# Project-PowerSwitch-005.net
KiCad netlist of a schematic drawn in EAGLE
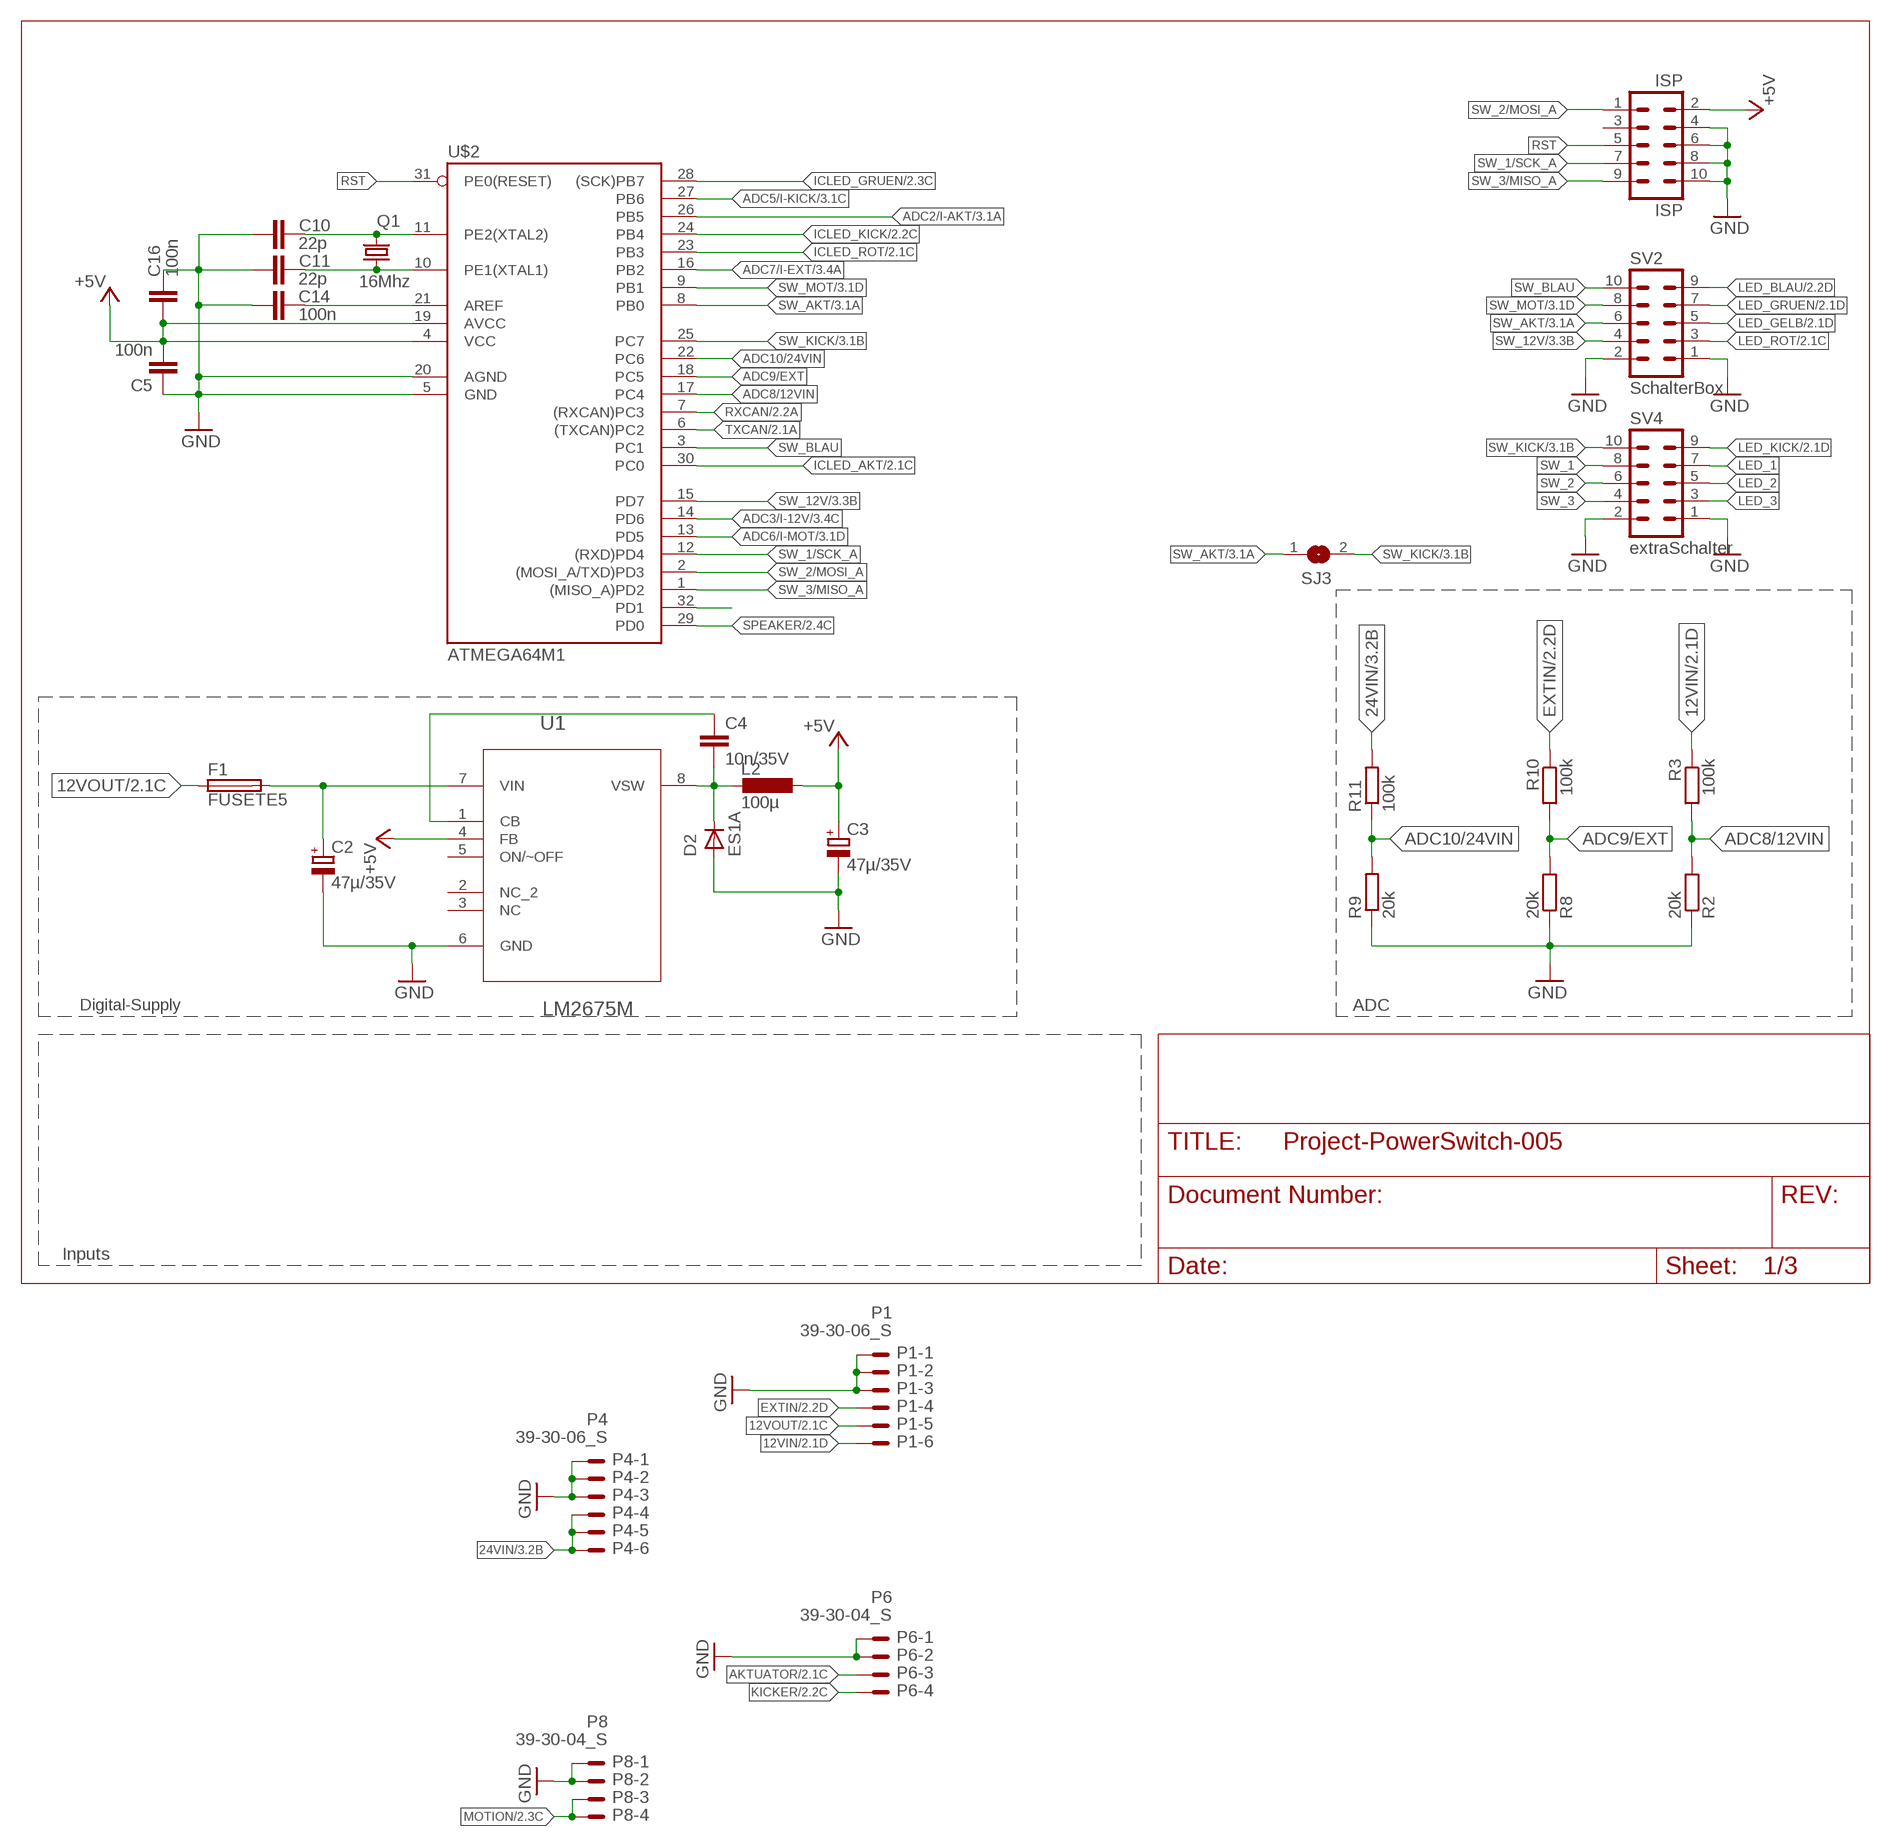
[diagram p0: schematic, sheet 1]
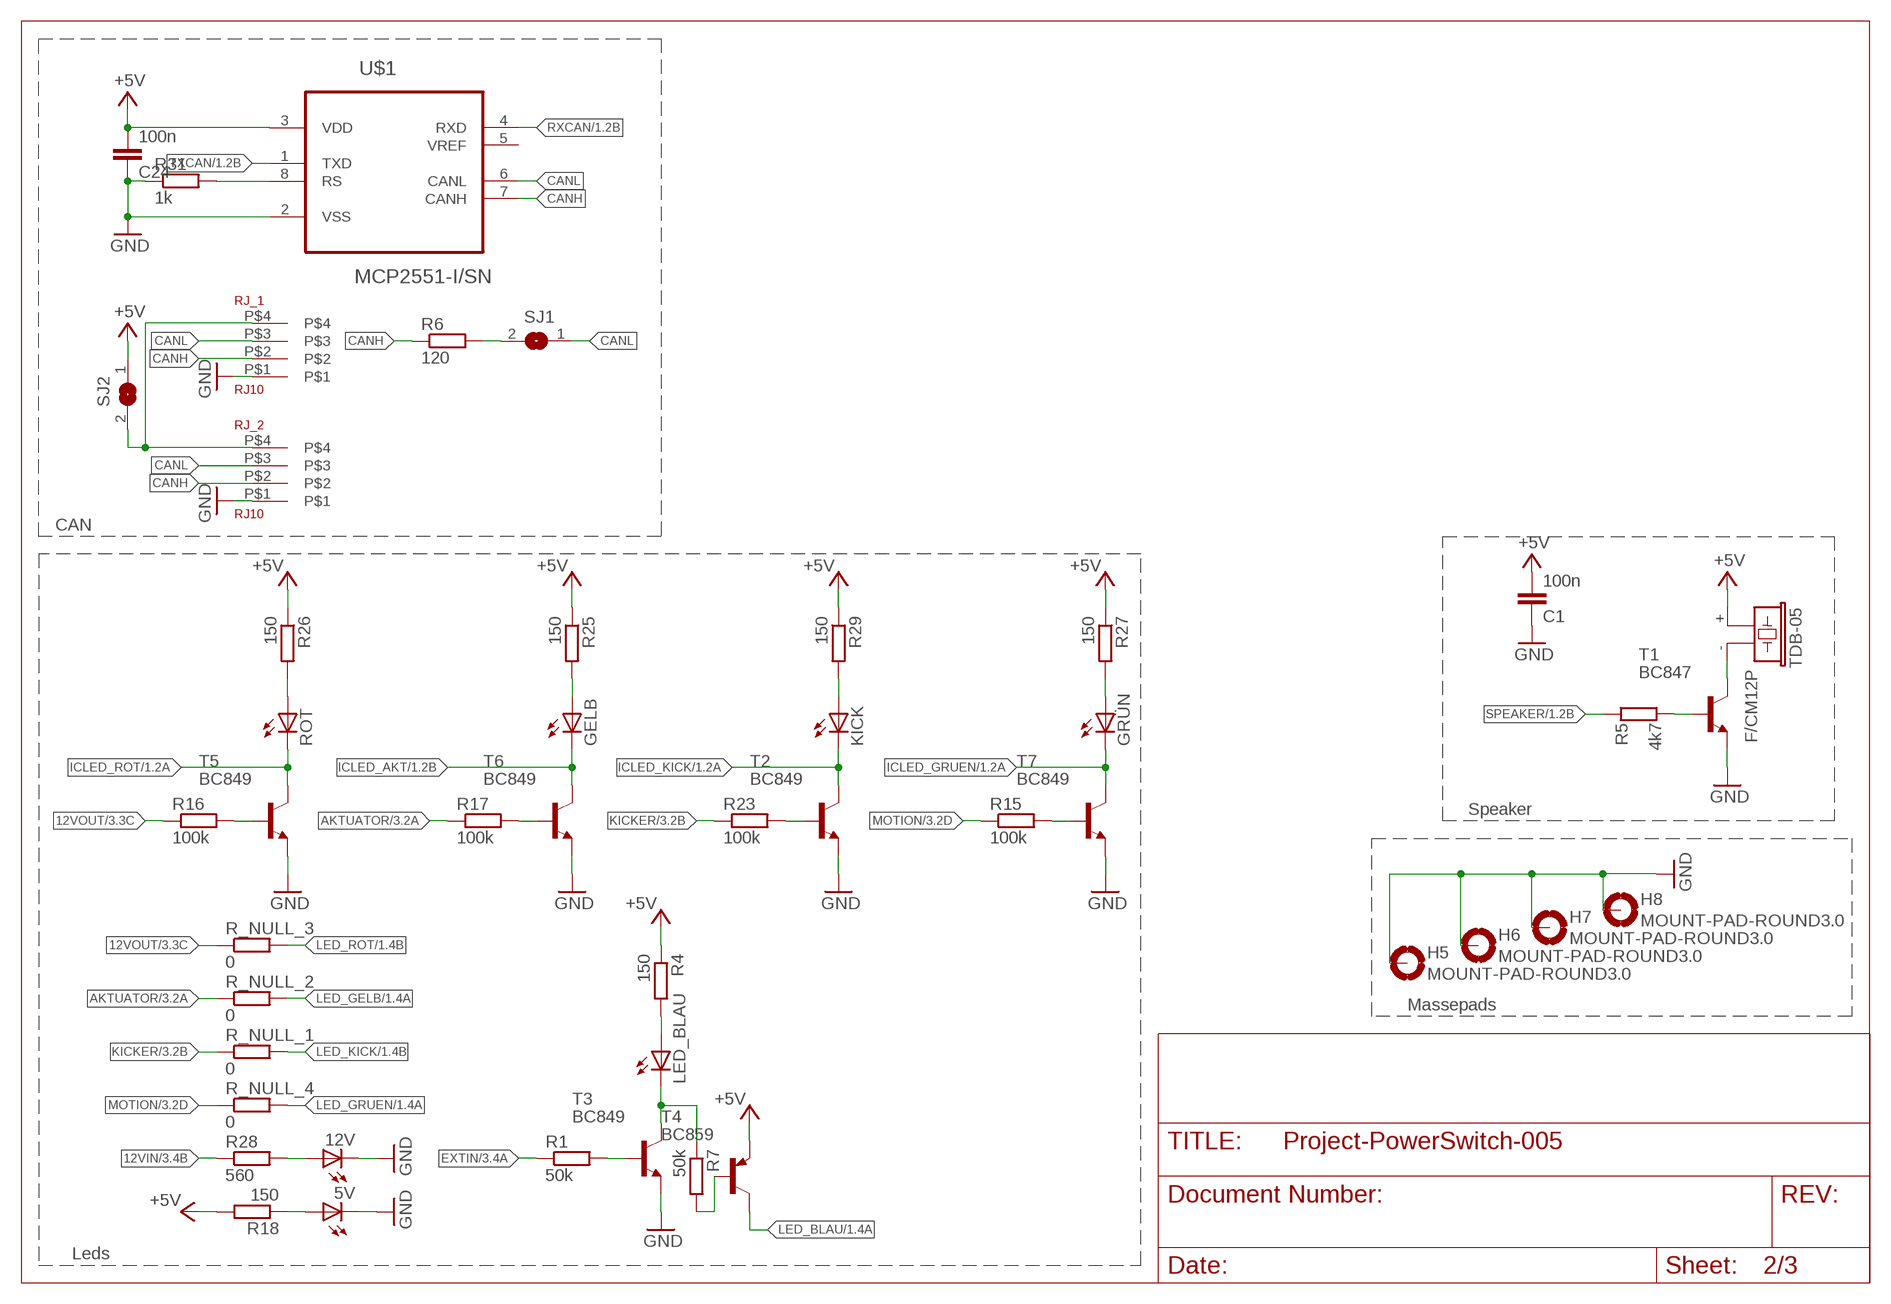
[diagram p1: schematic, sheet 2]
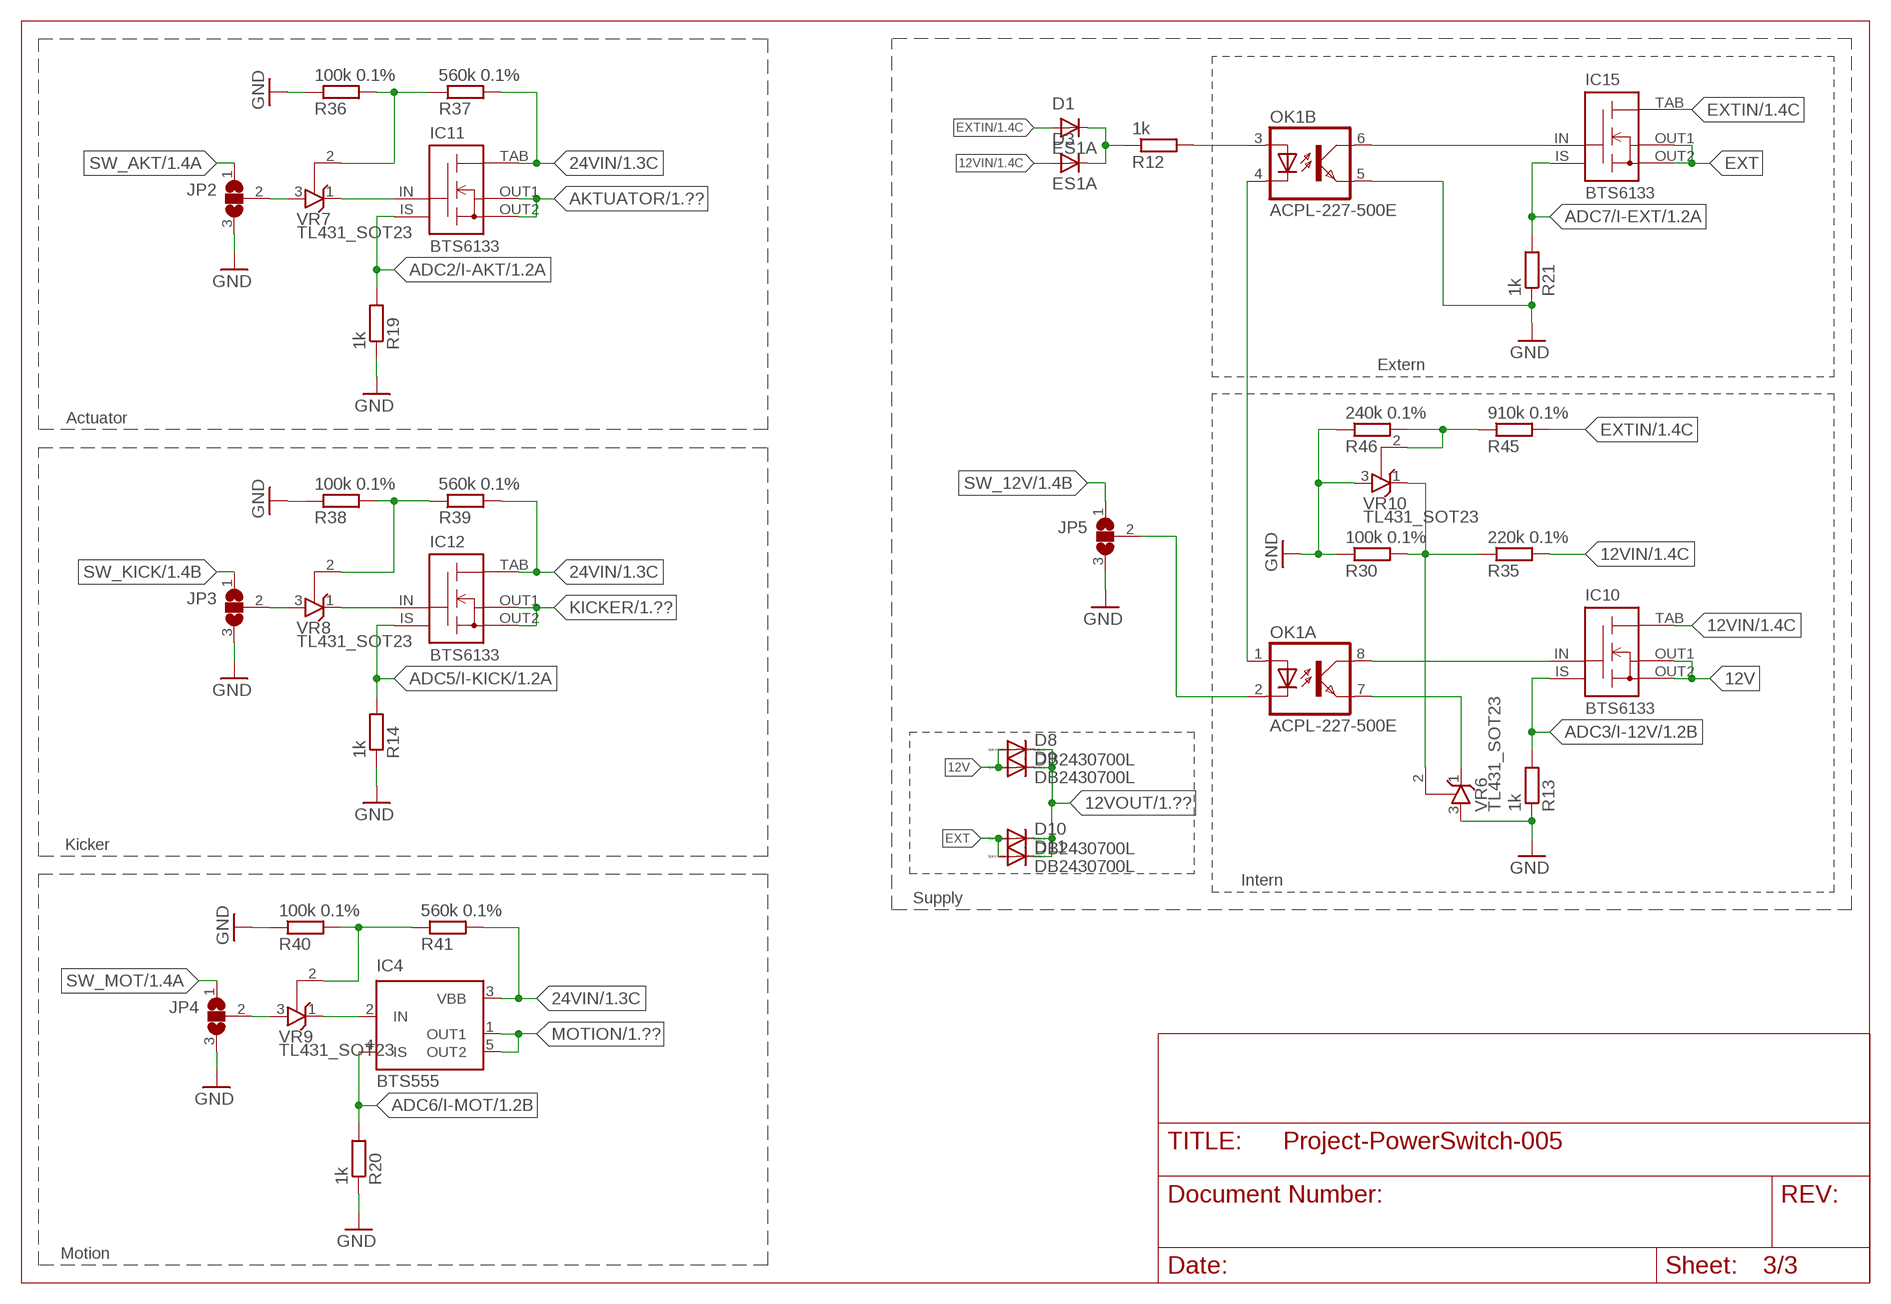
[diagram p2: schematic, sheet 3]

(export (version "E")
  (design (tool "Eeschema 10.0.6"))
  (components
    (comp (ref "C2")
      (value "47µ/35V")
      (footprint "eagle-import:PANASONIC_D")
      (libsource (lib "eagle-import") (part "CPOL-EUD"))
    )
    (comp (ref "C3")
      (value "47µ/35V")
      (footprint "eagle-import:PANASONIC_D")
      (libsource (lib "eagle-import") (part "CPOL-EUD"))
    )
    (comp (ref "C4")
      (value "10n/35V")
      (footprint "eagle-import:C0603")
      (libsource (lib "eagle-import") (part "C-EUC0603"))
    )
    (comp (ref "C5")
      (value "100n")
      (footprint "eagle-import:C0603")
      (libsource (lib "eagle-import") (part "C-EUC0603"))
    )
    (comp (ref "C10")
      (value "22p")
      (footprint "eagle-import:C0603")
      (libsource (lib "eagle-import") (part "C-EUC0603"))
    )
    (comp (ref "C11")
      (value "22p")
      (footprint "eagle-import:C0603")
      (libsource (lib "eagle-import") (part "C-EUC0603"))
    )
    (comp (ref "C14")
      (value "100n")
      (footprint "eagle-import:C0603")
      (libsource (lib "eagle-import") (part "C-EUC0603"))
    )
    (comp (ref "C16")
      (value "100n")
      (footprint "eagle-import:C0603")
      (libsource (lib "eagle-import") (part "C-EUC0603"))
    )
    (comp (ref "D2")
      (value "ES1A")
      (footprint "eagle-import:SMA-DO214AC")
      (libsource (lib "eagle-import") (part "GF1"))
    )
    (comp (ref "F1")
      (value "FUSETE5")
      (footprint "eagle-import:TE5")
      (libsource (lib "eagle-import") (part "FUSETE5"))
    )
    (comp (ref "ISP")
      (value "ISP")
      (footprint "eagle-import:ML10")
      (libsource (lib "eagle-import") (part "ML10"))
    )
    (comp (ref "L2")
      (value "100µ")
      (footprint "eagle-import:PISM")
      (libsource (lib "eagle-import") (part "L-EUPISM"))
    )
    (comp (ref "P1")
      (value "39-30-06_S")
      (footprint "eagle-import:39-30-_06_")
      (libsource (lib "eagle-import") (part "39-30-?06?_S"))
    )
    (comp (ref "P4")
      (value "39-30-06_S")
      (footprint "eagle-import:39-30-_06_")
      (libsource (lib "eagle-import") (part "39-30-?06?_S"))
    )
    (comp (ref "P6")
      (value "39-30-04_S")
      (footprint "eagle-import:39-30-_04_")
      (libsource (lib "eagle-import") (part "39-30-?04?_S"))
    )
    (comp (ref "P8")
      (value "39-30-04_S")
      (footprint "eagle-import:39-30-_04_")
      (libsource (lib "eagle-import") (part "39-30-?04?_S"))
    )
    (comp (ref "Q1")
      (value "16Mhz")
      (footprint "eagle-import:HC49UP")
      (libsource (lib "eagle-import") (part "CRYSTALHC49UP"))
    )
    (comp (ref "R2")
      (value "20k")
      (footprint "eagle-import:R0805")
      (libsource (lib "eagle-import") (part "R-EU_R0805"))
    )
    (comp (ref "R3")
      (value "100k")
      (footprint "eagle-import:R0805")
      (libsource (lib "eagle-import") (part "R-EU_R0805"))
    )
    (comp (ref "R8")
      (value "20k")
      (footprint "eagle-import:R0805")
      (libsource (lib "eagle-import") (part "R-EU_R0805"))
    )
    (comp (ref "R9")
      (value "20k")
      (footprint "eagle-import:R0805")
      (libsource (lib "eagle-import") (part "R-EU_R0805"))
    )
    (comp (ref "R10")
      (value "100k")
      (footprint "eagle-import:R0805")
      (libsource (lib "eagle-import") (part "R-EU_R0805"))
    )
    (comp (ref "R11")
      (value "100k")
      (footprint "eagle-import:R0805")
      (libsource (lib "eagle-import") (part "R-EU_R0805"))
    )
    (comp (ref "SJ3") (value "SJ") (footprint "eagle-import:SJ") (libsource (lib "eagle-import") (part "SJ")))
    (comp (ref "SV2")
      (value "SchalterBox")
      (footprint "eagle-import:ML10")
      (libsource (lib "eagle-import") (part "ML10"))
    )
    (comp (ref "SV4")
      (value "extraSchalter")
      (footprint "eagle-import:ML10")
      (libsource (lib "eagle-import") (part "ML10"))
    )
    (comp (ref "U$2")
      (value "ATMEGA64M1")
      (footprint "eagle-import:TQFP32-08")
      (libsource (lib "eagle-import") (part "ATMEGA64M1"))
    )
    (comp (ref "U1")
      (value "LM2675M")
      (footprint "eagle-import:SOIC127P620X175-8N")
      (fields (field (name "MPN") "LM2675M-3.3"))
      (libsource (lib "eagle-import") (part "LM2675M-3.3"))
    )
    (comp (ref "D1")
      (value "ES1A")
      (footprint "eagle-import:SMA-DO214AC")
      (libsource (lib "eagle-import") (part "GF1"))
    )
    (comp (ref "D3")
      (value "ES1A")
      (footprint "eagle-import:SMA-DO214AC")
      (libsource (lib "eagle-import") (part "GF1"))
    )
    (comp (ref "D8")
      (value "DB2430700L")
      (footprint "eagle-import:TMINIP2-F2-B")
      (libsource (lib "eagle-import") (part "DB2430700L"))
    )
    (comp (ref "D9")
      (value "DB2430700L")
      (footprint "eagle-import:TMINIP2-F2-B")
      (libsource (lib "eagle-import") (part "DB2430700L"))
    )
    (comp (ref "D10")
      (value "DB2430700L")
      (footprint "eagle-import:TMINIP2-F2-B")
      (libsource (lib "eagle-import") (part "DB2430700L"))
    )
    (comp (ref "D11")
      (value "DB2430700L")
      (footprint "eagle-import:TMINIP2-F2-B")
      (libsource (lib "eagle-import") (part "DB2430700L"))
    )
    (comp (ref "IC4")
      (value "BTS555")
      (footprint "eagle-import:TO220-51")
      (fields (field (name "MF") "FARNELL") (field (name "MPN") "BTS555."))
      (libsource (lib "eagle-import") (part "BTS555"))
    )
    (comp (ref "IC10")
      (value "BTS6133")
      (footprint "eagle-import:TO252-51")
      (libsource (lib "eagle-import") (part "BTS6133"))
    )
    (comp (ref "IC11")
      (value "BTS6133")
      (footprint "eagle-import:TO252-51")
      (libsource (lib "eagle-import") (part "BTS6133"))
    )
    (comp (ref "IC12")
      (value "BTS6133")
      (footprint "eagle-import:TO252-51")
      (libsource (lib "eagle-import") (part "BTS6133"))
    )
    (comp (ref "IC15")
      (value "BTS6133")
      (footprint "eagle-import:TO252-51")
      (libsource (lib "eagle-import") (part "BTS6133"))
    )
    (comp (ref "JP2")
      (value "SJ2W")
      (footprint "eagle-import:SJ_2")
      (libsource (lib "eagle-import") (part "SJ2W"))
    )
    (comp (ref "JP3")
      (value "SJ2W")
      (footprint "eagle-import:SJ_2")
      (libsource (lib "eagle-import") (part "SJ2W"))
    )
    (comp (ref "JP4")
      (value "SJ2W")
      (footprint "eagle-import:SJ_2")
      (libsource (lib "eagle-import") (part "SJ2W"))
    )
    (comp (ref "JP5")
      (value "SJ2W")
      (footprint "eagle-import:SJ_2")
      (libsource (lib "eagle-import") (part "SJ2W"))
    )
    (comp (ref "OK1")
      (value "ACPL-227-500E")
      (footprint "eagle-import:SOIC08")
      (fields (field (name "MF") "VISHAY/TELEFUNKEN") (field (name "MPN") "ILD207T"))
      (libsource (lib "eagle-import") (part "ILD207"))
    )
    (comp (ref "R12")
      (value "1k")
      (footprint "eagle-import:R0805")
      (libsource (lib "eagle-import") (part "R-EU_R0805"))
    )
    (comp (ref "R13")
      (value "1k")
      (footprint "eagle-import:R0805")
      (libsource (lib "eagle-import") (part "R-EU_R0805"))
    )
    (comp (ref "R14")
      (value "1k")
      (footprint "eagle-import:R0805")
      (libsource (lib "eagle-import") (part "R-EU_R0805"))
    )
    (comp (ref "R19")
      (value "1k")
      (footprint "eagle-import:R0805")
      (libsource (lib "eagle-import") (part "R-EU_R0805"))
    )
    (comp (ref "R20")
      (value "1k")
      (footprint "eagle-import:R0805")
      (libsource (lib "eagle-import") (part "R-EU_R0805"))
    )
    (comp (ref "R21")
      (value "1k")
      (footprint "eagle-import:R0805")
      (libsource (lib "eagle-import") (part "R-EU_R0805"))
    )
    (comp (ref "R30")
      (value "100k 0.1%")
      (footprint "eagle-import:R0805")
      (libsource (lib "eagle-import") (part "R-EU_R0805"))
    )
    (comp (ref "R35")
      (value "220k 0.1%")
      (footprint "eagle-import:R0805")
      (libsource (lib "eagle-import") (part "R-EU_R0805"))
    )
    (comp (ref "R36")
      (value "100k 0.1%")
      (footprint "eagle-import:R0805")
      (libsource (lib "eagle-import") (part "R-EU_R0805"))
    )
    (comp (ref "R37")
      (value "560k 0.1%")
      (footprint "eagle-import:R0805")
      (libsource (lib "eagle-import") (part "R-EU_R0805"))
    )
    (comp (ref "R38")
      (value "100k 0.1%")
      (footprint "eagle-import:R0805")
      (libsource (lib "eagle-import") (part "R-EU_R0805"))
    )
    (comp (ref "R39")
      (value "560k 0.1%")
      (footprint "eagle-import:R0805")
      (libsource (lib "eagle-import") (part "R-EU_R0805"))
    )
    (comp (ref "R40")
      (value "100k 0.1%")
      (footprint "eagle-import:R0805")
      (libsource (lib "eagle-import") (part "R-EU_R0805"))
    )
    (comp (ref "R41")
      (value "560k 0.1%")
      (footprint "eagle-import:R0805")
      (libsource (lib "eagle-import") (part "R-EU_R0805"))
    )
    (comp (ref "R45")
      (value "910k 0.1%")
      (footprint "eagle-import:R0805")
      (libsource (lib "eagle-import") (part "R-EU_R0805"))
    )
    (comp (ref "R46")
      (value "240k 0.1%")
      (footprint "eagle-import:R0805")
      (libsource (lib "eagle-import") (part "R-EU_R0805"))
    )
    (comp (ref "VR6")
      (value "TL431_SOT23")
      (footprint "eagle-import:SOT23")
      (libsource (lib "eagle-import") (part "TL431_SOT23"))
    )
    (comp (ref "VR7")
      (value "TL431_SOT23")
      (footprint "eagle-import:SOT23")
      (libsource (lib "eagle-import") (part "TL431_SOT23"))
    )
    (comp (ref "VR8")
      (value "TL431_SOT23")
      (footprint "eagle-import:SOT23")
      (libsource (lib "eagle-import") (part "TL431_SOT23"))
    )
    (comp (ref "VR9")
      (value "TL431_SOT23")
      (footprint "eagle-import:SOT23")
      (libsource (lib "eagle-import") (part "TL431_SOT23"))
    )
    (comp (ref "VR10")
      (value "TL431_SOT23")
      (footprint "eagle-import:SOT23")
      (libsource (lib "eagle-import") (part "TL431_SOT23"))
    )
    (comp (ref "5V")
      (value "LEDCHIPLED_0805")
      (footprint "eagle-import:CHIPLED_0805")
      (libsource (lib "eagle-import") (part "LEDCHIPLED_0805"))
    )
    (comp (ref "12V")
      (value "LEDCHIPLED_0805")
      (footprint "eagle-import:CHIPLED_0805")
      (libsource (lib "eagle-import") (part "LEDCHIPLED_0805"))
    )
    (comp (ref "C1")
      (value "100n")
      (footprint "eagle-import:C0603")
      (libsource (lib "eagle-import") (part "C-EUC0603"))
    )
    (comp (ref "C24")
      (value "100n")
      (footprint "eagle-import:C0603")
      (libsource (lib "eagle-import") (part "C-EUC0603"))
    )
    (comp (ref "GELB")
      (value "LEDCHIPLED_0805")
      (footprint "eagle-import:CHIPLED_0805")
      (libsource (lib "eagle-import") (part "LEDCHIPLED_0805"))
    )
    (comp (ref "GRÜN")
      (value "LEDCHIPLED_0805")
      (footprint "eagle-import:CHIPLED_0805")
      (libsource (lib "eagle-import") (part "LEDCHIPLED_0805"))
    )
    (comp (ref "H5")
      (value "MOUNT-PAD-ROUND3.0")
      (footprint "eagle-import:3,0-PAD")
      (libsource (lib "eagle-import") (part "MOUNT-PAD-ROUND3.0"))
    )
    (comp (ref "H6")
      (value "MOUNT-PAD-ROUND3.0")
      (footprint "eagle-import:3,0-PAD")
      (libsource (lib "eagle-import") (part "MOUNT-PAD-ROUND3.0"))
    )
    (comp (ref "H7")
      (value "MOUNT-PAD-ROUND3.0")
      (footprint "eagle-import:3,0-PAD")
      (libsource (lib "eagle-import") (part "MOUNT-PAD-ROUND3.0"))
    )
    (comp (ref "H8")
      (value "MOUNT-PAD-ROUND3.0")
      (footprint "eagle-import:3,0-PAD")
      (libsource (lib "eagle-import") (part "MOUNT-PAD-ROUND3.0"))
    )
    (comp (ref "KICK")
      (value "LEDCHIPLED_0805")
      (footprint "eagle-import:CHIPLED_0805")
      (libsource (lib "eagle-import") (part "LEDCHIPLED_0805"))
    )
    (comp (ref "LED_BLAU")
      (value "LEDCHIPLED_0805")
      (footprint "eagle-import:CHIPLED_0805")
      (libsource (lib "eagle-import") (part "LEDCHIPLED_0805"))
    )
    (comp (ref "R1")
      (value "50k")
      (footprint "eagle-import:R0805")
      (libsource (lib "eagle-import") (part "R-EU_R0805"))
    )
    (comp (ref "R4")
      (value "150")
      (footprint "eagle-import:R0805")
      (libsource (lib "eagle-import") (part "R-EU_R0805"))
    )
    (comp (ref "R5")
      (value "4k7")
      (footprint "eagle-import:R0805")
      (libsource (lib "eagle-import") (part "R-EU_R0805"))
    )
    (comp (ref "R6")
      (value "120")
      (footprint "eagle-import:M0805")
      (libsource (lib "eagle-import") (part "R-EU_M0805"))
    )
    (comp (ref "R7")
      (value "50k")
      (footprint "eagle-import:R0805")
      (libsource (lib "eagle-import") (part "R-EU_R0805"))
    )
    (comp (ref "R15")
      (value "100k")
      (footprint "eagle-import:R0805")
      (libsource (lib "eagle-import") (part "R-EU_R0805"))
    )
    (comp (ref "R16")
      (value "100k")
      (footprint "eagle-import:R0805")
      (libsource (lib "eagle-import") (part "R-EU_R0805"))
    )
    (comp (ref "R17")
      (value "100k")
      (footprint "eagle-import:R0805")
      (libsource (lib "eagle-import") (part "R-EU_R0805"))
    )
    (comp (ref "R18")
      (value "150")
      (footprint "eagle-import:R0805")
      (libsource (lib "eagle-import") (part "R-EU_R0805"))
    )
    (comp (ref "R23")
      (value "100k")
      (footprint "eagle-import:R0805")
      (libsource (lib "eagle-import") (part "R-EU_R0805"))
    )
    (comp (ref "R25")
      (value "150")
      (footprint "eagle-import:R0805")
      (libsource (lib "eagle-import") (part "R-EU_R0805"))
    )
    (comp (ref "R26")
      (value "150")
      (footprint "eagle-import:R0805")
      (libsource (lib "eagle-import") (part "R-EU_R0805"))
    )
    (comp (ref "R27")
      (value "150")
      (footprint "eagle-import:R0805")
      (libsource (lib "eagle-import") (part "R-EU_R0805"))
    )
    (comp (ref "R28")
      (value "560")
      (footprint "eagle-import:R0805")
      (libsource (lib "eagle-import") (part "R-EU_R0805"))
    )
    (comp (ref "R29")
      (value "150")
      (footprint "eagle-import:R0805")
      (libsource (lib "eagle-import") (part "R-EU_R0805"))
    )
    (comp (ref "R31")
      (value "1k")
      (footprint "eagle-import:R0805")
      (libsource (lib "eagle-import") (part "R-EU_R0805"))
    )
    (comp (ref "RJ_1")
      (value "RJ10")
      (footprint "eagle-import:RJ10")
      (libsource (lib "eagle-import") (part "RJ10"))
    )
    (comp (ref "RJ_2")
      (value "RJ10")
      (footprint "eagle-import:RJ10")
      (libsource (lib "eagle-import") (part "RJ10"))
    )
    (comp (ref "ROT")
      (value "LEDCHIPLED_0805")
      (footprint "eagle-import:CHIPLED_0805")
      (libsource (lib "eagle-import") (part "LEDCHIPLED_0805"))
    )
    (comp (ref "R_NULL_1")
      (value "0")
      (footprint "eagle-import:R0402")
      (libsource (lib "eagle-import") (part "R-EU_R0402"))
    )
    (comp (ref "R_NULL_2")
      (value "0")
      (footprint "eagle-import:R0402")
      (libsource (lib "eagle-import") (part "R-EU_R0402"))
    )
    (comp (ref "R_NULL_3")
      (value "0")
      (footprint "eagle-import:R0402")
      (libsource (lib "eagle-import") (part "R-EU_R0402"))
    )
    (comp (ref "R_NULL_4")
      (value "0")
      (footprint "eagle-import:R0402")
      (libsource (lib "eagle-import") (part "R-EU_R0402"))
    )
    (comp (ref "SJ1") (value "SJ") (footprint "eagle-import:SJ") (libsource (lib "eagle-import") (part "SJ")))
    (comp (ref "SJ2") (value "SJ") (footprint "eagle-import:SJ") (libsource (lib "eagle-import") (part "SJ")))
    (comp (ref "T1")
      (value "BC847")
      (footprint "eagle-import:SOT23")
      (libsource (lib "eagle-import") (part "BC847"))
    )
    (comp (ref "T2")
      (value "BC849")
      (footprint "eagle-import:SOT23")
      (libsource (lib "eagle-import") (part "BC849"))
    )
    (comp (ref "T3")
      (value "BC849")
      (footprint "eagle-import:SOT23")
      (libsource (lib "eagle-import") (part "BC849"))
    )
    (comp (ref "T4")
      (value "BC859")
      (footprint "eagle-import:SOT23-BEC")
      (libsource (lib "eagle-import") (part "-PNP-SOT23-BECBC858C"))
    )
    (comp (ref "T5")
      (value "BC849")
      (footprint "eagle-import:SOT23")
      (libsource (lib "eagle-import") (part "BC849"))
    )
    (comp (ref "T6")
      (value "BC849")
      (footprint "eagle-import:SOT23")
      (libsource (lib "eagle-import") (part "BC849"))
    )
    (comp (ref "T7")
      (value "BC849")
      (footprint "eagle-import:SOT23")
      (libsource (lib "eagle-import") (part "BC849"))
    )
    (comp (ref "TDB-05")
      (value "F/CM12P")
      (footprint "eagle-import:F_CM12P")
      (libsource (lib "eagle-import") (part "F/CM12P"))
    )
    (comp (ref "U$1")
      (value "MCP2551-I/SN")
      (footprint "eagle-import:SOIC127P600X175-8N")
      (libsource (lib "eagle-import") (part "MCP2551-I/SN"))
    )
  )
  (nets
    (net (code "1") (name "+5V") (class "Default")
      (node (ref "C1") (pin "2") (pinfunction "2_2") (pintype "passive"))
      (node (ref "C16") (pin "1") (pinfunction "1_1") (pintype "passive"))
      (node (ref "C24") (pin "2") (pinfunction "2_2") (pintype "passive"))
      (node (ref "C3") (pin "+") (pinfunction "+_+") (pintype "passive"))
      (node (ref "C5") (pin "2") (pinfunction "2_2") (pintype "passive"))
      (node (ref "ISP") (pin "2") (pinfunction "2_2") (pintype "passive"))
      (node (ref "L2") (pin "1") (pinfunction "1_1") (pintype "passive"))
      (node (ref "R18") (pin "2") (pinfunction "2_2") (pintype "passive"))
      (node (ref "R25") (pin "1") (pinfunction "1_1") (pintype "passive"))
      (node (ref "R26") (pin "1") (pinfunction "1_1") (pintype "passive"))
      (node (ref "R27") (pin "1") (pinfunction "1_1") (pintype "passive"))
      (node (ref "R29") (pin "1") (pinfunction "1_1") (pintype "passive"))
      (node (ref "R4") (pin "1") (pinfunction "1_1") (pintype "passive"))
      (node (ref "SJ2") (pin "1") (pinfunction "1_1") (pintype "passive"))
      (node (ref "T4") (pin "E") (pinfunction "E_E") (pintype "passive"))
      (node (ref "TDB-05") (pin "+") (pinfunction "1_+") (pintype "passive"))
      (node (ref "U$1") (pin "3") (pinfunction "VDD_3") (pintype "power_in"))
      (node (ref "U$2") (pin "19") (pinfunction "AVCC_19") (pintype "bidirectional"))
      (node (ref "U$2") (pin "4") (pinfunction "VCC_4") (pintype "bidirectional"))
      (node (ref "U1") (pin "4") (pinfunction "FB_4") (pintype "input"))
    )
    (net (code "2") (name "12V") (class "Default")
      (node (ref "D8") (pin "A") (pinfunction "A_A") (pintype "passive"))
      (node (ref "D9") (pin "A") (pinfunction "A_A") (pintype "passive"))
      (node (ref "IC10") (pin "OUT1") (pinfunction "OUT_OUT1") (pintype "passive"))
      (node (ref "IC10") (pin "OUT2") (pinfunction "OUT_OUT2") (pintype "passive"))
    )
    (net (code "3") (name "12VIN") (class "Default")
      (node (ref "D3") (pin "A") (pinfunction "A_A") (pintype "passive"))
      (node (ref "IC10") (pin "TAB") (pinfunction "VBB_TAB") (pintype "power_in"))
      (node (ref "P1") (pin "6") (pinfunction "P_6") (pintype "passive"))
      (node (ref "R28") (pin "1") (pinfunction "1_1") (pintype "passive"))
      (node (ref "R3") (pin "1") (pinfunction "1_1") (pintype "passive"))
      (node (ref "R35") (pin "2") (pinfunction "2_2") (pintype "passive"))
    )
    (net (code "4") (name "12VOUT") (class "Default")
      (node (ref "D10") (pin "C") (pinfunction "C_C") (pintype "passive"))
      (node (ref "D11") (pin "C") (pinfunction "C_C") (pintype "passive"))
      (node (ref "D8") (pin "C") (pinfunction "C_C") (pintype "passive"))
      (node (ref "D9") (pin "C") (pinfunction "C_C") (pintype "passive"))
      (node (ref "F1") (pin "1") (pinfunction "1_1") (pintype "passive"))
      (node (ref "P1") (pin "5") (pinfunction "P_5") (pintype "passive"))
      (node (ref "R16") (pin "1") (pinfunction "1_1") (pintype "passive"))
      (node (ref "R_NULL_3") (pin "1") (pinfunction "1_1") (pintype "passive"))
    )
    (net (code "5") (name "24VIN") (class "Default")
      (node (ref "IC11") (pin "TAB") (pinfunction "VBB_TAB") (pintype "power_in"))
      (node (ref "IC12") (pin "TAB") (pinfunction "VBB_TAB") (pintype "power_in"))
      (node (ref "IC4") (pin "3") (pinfunction "VBB_3") (pintype "passive"))
      (node (ref "P4") (pin "4") (pinfunction "P_4") (pintype "passive"))
      (node (ref "P4") (pin "5") (pinfunction "P_5") (pintype "passive"))
      (node (ref "P4") (pin "6") (pinfunction "P_6") (pintype "passive"))
      (node (ref "R11") (pin "2") (pinfunction "2_2") (pintype "passive"))
      (node (ref "R37") (pin "2") (pinfunction "2_2") (pintype "passive"))
      (node (ref "R39") (pin "2") (pinfunction "2_2") (pintype "passive"))
      (node (ref "R41") (pin "2") (pinfunction "2_2") (pintype "passive"))
    )
    (net (code "6") (name "ADC2{slash}I-AKT") (class "Default")
      (node (ref "IC11") (pin "IS") (pinfunction "IS_IS") (pintype "passive"))
      (node (ref "R19") (pin "2") (pinfunction "2_2") (pintype "passive"))
      (node (ref "U$2") (pin "26") (pinfunction "PB5_26") (pintype "bidirectional"))
    )
    (net (code "7") (name "ADC3{slash}I-12V") (class "Default")
      (node (ref "IC10") (pin "IS") (pinfunction "IS_IS") (pintype "passive"))
      (node (ref "R13") (pin "2") (pinfunction "2_2") (pintype "passive"))
      (node (ref "U$2") (pin "14") (pinfunction "PD6_14") (pintype "bidirectional"))
    )
    (net (code "8") (name "ADC5{slash}I-KICK") (class "Default")
      (node (ref "IC12") (pin "IS") (pinfunction "IS_IS") (pintype "passive"))
      (node (ref "R14") (pin "2") (pinfunction "2_2") (pintype "passive"))
      (node (ref "U$2") (pin "27") (pinfunction "PB6_27") (pintype "bidirectional"))
    )
    (net (code "9") (name "ADC6{slash}I-MOT") (class "Default")
      (node (ref "IC4") (pin "4") (pinfunction "IS_4") (pintype "passive"))
      (node (ref "R20") (pin "2") (pinfunction "2_2") (pintype "passive"))
      (node (ref "U$2") (pin "13") (pinfunction "PD5_13") (pintype "bidirectional"))
    )
    (net (code "10") (name "ADC7{slash}I-EXT") (class "Default")
      (node (ref "IC15") (pin "IS") (pinfunction "IS_IS") (pintype "passive"))
      (node (ref "R21") (pin "2") (pinfunction "2_2") (pintype "passive"))
      (node (ref "U$2") (pin "16") (pinfunction "PB2_16") (pintype "bidirectional"))
    )
    (net (code "11") (name "ADC8{slash}12VIN") (class "Default")
      (node (ref "R2") (pin "2") (pinfunction "2_2") (pintype "passive"))
      (node (ref "R3") (pin "2") (pinfunction "2_2") (pintype "passive"))
      (node (ref "U$2") (pin "17") (pinfunction "PC4_17") (pintype "bidirectional"))
    )
    (net (code "12") (name "ADC9{slash}EXT") (class "Default")
      (node (ref "R10") (pin "2") (pinfunction "2_2") (pintype "passive"))
      (node (ref "R8") (pin "2") (pinfunction "2_2") (pintype "passive"))
      (node (ref "U$2") (pin "18") (pinfunction "PC5_18") (pintype "bidirectional"))
    )
    (net (code "13") (name "ADC10{slash}24VIN") (class "Default")
      (node (ref "R11") (pin "1") (pinfunction "1_1") (pintype "passive"))
      (node (ref "R9") (pin "2") (pinfunction "2_2") (pintype "passive"))
      (node (ref "U$2") (pin "22") (pinfunction "PC6_22") (pintype "bidirectional"))
    )
    (net (code "14") (name "AKTUATOR") (class "Default")
      (node (ref "IC11") (pin "OUT1") (pinfunction "OUT_OUT1") (pintype "passive"))
      (node (ref "IC11") (pin "OUT2") (pinfunction "OUT_OUT2") (pintype "passive"))
      (node (ref "P6") (pin "3") (pinfunction "P_3") (pintype "passive"))
      (node (ref "R17") (pin "1") (pinfunction "1_1") (pintype "passive"))
      (node (ref "R_NULL_2") (pin "1") (pinfunction "1_1") (pintype "passive"))
    )
    (net (code "15") (name "CANH") (class "Default")
      (node (ref "R6") (pin "1") (pinfunction "1_1") (pintype "passive"))
      (node (ref "RJ_1") (pin "P$2") (pinfunction "P$2_P$2") (pintype "bidirectional"))
      (node (ref "RJ_2") (pin "P$2") (pinfunction "P$2_P$2") (pintype "bidirectional"))
      (node (ref "U$1") (pin "7") (pinfunction "CANH_7") (pintype "bidirectional"))
    )
    (net (code "16") (name "CANL") (class "Default")
      (node (ref "RJ_1") (pin "P$3") (pinfunction "P$3_P$3") (pintype "bidirectional"))
      (node (ref "RJ_2") (pin "P$3") (pinfunction "P$3_P$3") (pintype "bidirectional"))
      (node (ref "SJ1") (pin "1") (pinfunction "1_1") (pintype "passive"))
      (node (ref "U$1") (pin "6") (pinfunction "CANL_6") (pintype "bidirectional"))
    )
    (net (code "17") (name "EXT") (class "Default")
      (node (ref "D10") (pin "A") (pinfunction "A_A") (pintype "passive"))
      (node (ref "D11") (pin "A") (pinfunction "A_A") (pintype "passive"))
      (node (ref "IC15") (pin "OUT1") (pinfunction "OUT_OUT1") (pintype "passive"))
      (node (ref "IC15") (pin "OUT2") (pinfunction "OUT_OUT2") (pintype "passive"))
    )
    (net (code "18") (name "EXTIN") (class "Default")
      (node (ref "D1") (pin "A") (pinfunction "A_A") (pintype "passive"))
      (node (ref "IC15") (pin "TAB") (pinfunction "VBB_TAB") (pintype "power_in"))
      (node (ref "P1") (pin "4") (pinfunction "P_4") (pintype "passive"))
      (node (ref "R1") (pin "1") (pinfunction "1_1") (pintype "passive"))
      (node (ref "R10") (pin "1") (pinfunction "1_1") (pintype "passive"))
      (node (ref "R45") (pin "2") (pinfunction "2_2") (pintype "passive"))
    )
    (net (code "19") (name "GND") (class "Default")
      (node (ref "12V") (pin "C") (pinfunction "C_C") (pintype "passive"))
      (node (ref "5V") (pin "C") (pinfunction "C_C") (pintype "passive"))
      (node (ref "C1") (pin "1") (pinfunction "1_1") (pintype "passive"))
      (node (ref "C10") (pin "1") (pinfunction "1_1") (pintype "passive"))
      (node (ref "C11") (pin "1") (pinfunction "1_1") (pintype "passive"))
      (node (ref "C14") (pin "1") (pinfunction "1_1") (pintype "passive"))
      (node (ref "C16") (pin "2") (pinfunction "2_2") (pintype "passive"))
      (node (ref "C2") (pin "-") (pinfunction "-_-") (pintype "passive"))
      (node (ref "C24") (pin "1") (pinfunction "1_1") (pintype "passive"))
      (node (ref "C3") (pin "-") (pinfunction "-_-") (pintype "passive"))
      (node (ref "C5") (pin "1") (pinfunction "1_1") (pintype "passive"))
      (node (ref "D2") (pin "A") (pinfunction "A_A") (pintype "passive"))
      (node (ref "H5") (pin "B3,0") (pinfunction "MOUNT_B3,0") (pintype "passive"))
      (node (ref "H6") (pin "B3,0") (pinfunction "MOUNT_B3,0") (pintype "passive"))
      (node (ref "H7") (pin "B3,0") (pinfunction "MOUNT_B3,0") (pintype "passive"))
      (node (ref "H8") (pin "B3,0") (pinfunction "MOUNT_B3,0") (pintype "passive"))
      (node (ref "ISP") (pin "10") (pinfunction "10_10") (pintype "passive"))
      (node (ref "ISP") (pin "4") (pinfunction "4_4") (pintype "passive"))
      (node (ref "ISP") (pin "6") (pinfunction "6_6") (pintype "passive"))
      (node (ref "ISP") (pin "8") (pinfunction "8_8") (pintype "passive"))
      (node (ref "JP2") (pin "3") (pinfunction "3_3") (pintype "passive"))
      (node (ref "JP3") (pin "3") (pinfunction "3_3") (pintype "passive"))
      (node (ref "JP4") (pin "3") (pinfunction "3_3") (pintype "passive"))
      (node (ref "JP5") (pin "3") (pinfunction "3_3") (pintype "passive"))
      (node (ref "OK1") (pin "5") (pinfunction "EMIT_5") (pintype "passive"))
      (node (ref "P1") (pin "1") (pinfunction "P_1") (pintype "passive"))
      (node (ref "P1") (pin "2") (pinfunction "P_2") (pintype "passive"))
      (node (ref "P1") (pin "3") (pinfunction "P_3") (pintype "passive"))
      (node (ref "P4") (pin "1") (pinfunction "P_1") (pintype "passive"))
      (node (ref "P4") (pin "2") (pinfunction "P_2") (pintype "passive"))
      (node (ref "P4") (pin "3") (pinfunction "P_3") (pintype "passive"))
      (node (ref "P6") (pin "1") (pinfunction "P_1") (pintype "passive"))
      (node (ref "P6") (pin "2") (pinfunction "P_2") (pintype "passive"))
      (node (ref "P8") (pin "1") (pinfunction "P_1") (pintype "passive"))
      (node (ref "P8") (pin "2") (pinfunction "P_2") (pintype "passive"))
      (node (ref "R13") (pin "1") (pinfunction "1_1") (pintype "passive"))
      (node (ref "R14") (pin "1") (pinfunction "1_1") (pintype "passive"))
      (node (ref "R19") (pin "1") (pinfunction "1_1") (pintype "passive"))
      (node (ref "R2") (pin "1") (pinfunction "1_1") (pintype "passive"))
      (node (ref "R20") (pin "1") (pinfunction "1_1") (pintype "passive"))
      (node (ref "R21") (pin "1") (pinfunction "1_1") (pintype "passive"))
      (node (ref "R30") (pin "1") (pinfunction "1_1") (pintype "passive"))
      (node (ref "R31") (pin "1") (pinfunction "1_1") (pintype "passive"))
      (node (ref "R36") (pin "1") (pinfunction "1_1") (pintype "passive"))
      (node (ref "R38") (pin "1") (pinfunction "1_1") (pintype "passive"))
      (node (ref "R40") (pin "1") (pinfunction "1_1") (pintype "passive"))
      (node (ref "R46") (pin "1") (pinfunction "1_1") (pintype "passive"))
      (node (ref "R8") (pin "1") (pinfunction "1_1") (pintype "passive"))
      (node (ref "R9") (pin "1") (pinfunction "1_1") (pintype "passive"))
      (node (ref "RJ_1") (pin "P$1") (pinfunction "P$1_P$1") (pintype "bidirectional"))
      (node (ref "RJ_2") (pin "P$1") (pinfunction "P$1_P$1") (pintype "bidirectional"))
      (node (ref "SV2") (pin "1") (pinfunction "1_1") (pintype "passive"))
      (node (ref "SV2") (pin "2") (pinfunction "2_2") (pintype "passive"))
      (node (ref "SV4") (pin "1") (pinfunction "1_1") (pintype "passive"))
      (node (ref "SV4") (pin "2") (pinfunction "2_2") (pintype "passive"))
      (node (ref "T1") (pin "2") (pinfunction "E_2") (pintype "passive"))
      (node (ref "T2") (pin "2") (pinfunction "E_2") (pintype "passive"))
      (node (ref "T3") (pin "2") (pinfunction "E_2") (pintype "passive"))
      (node (ref "T5") (pin "2") (pinfunction "E_2") (pintype "passive"))
      (node (ref "T6") (pin "2") (pinfunction "E_2") (pintype "passive"))
      (node (ref "T7") (pin "2") (pinfunction "E_2") (pintype "passive"))
      (node (ref "U$1") (pin "2") (pinfunction "VSS_2") (pintype "passive"))
      (node (ref "U$2") (pin "20") (pinfunction "AGND_20") (pintype "power_in"))
      (node (ref "U$2") (pin "5") (pinfunction "GND_5") (pintype "power_in"))
      (node (ref "U1") (pin "6") (pinfunction "GND_6") (pintype "passive"))
      (node (ref "VR10") (pin "3") (pinfunction "A_3") (pintype "passive"))
      (node (ref "VR6") (pin "3") (pinfunction "A_3") (pintype "passive"))
    )
    (net (code "20") (name "ICLED_AKT") (class "Default")
      (node (ref "GELB") (pin "C") (pinfunction "C_C") (pintype "passive"))
      (node (ref "T6") (pin "3") (pinfunction "C_3") (pintype "passive"))
      (node (ref "U$2") (pin "30") (pinfunction "PC0_30") (pintype "bidirectional"))
    )
    (net (code "21") (name "ICLED_GRUEN") (class "Default")
      (node (ref "GRÜN") (pin "C") (pinfunction "C_C") (pintype "passive"))
      (node (ref "T7") (pin "3") (pinfunction "C_3") (pintype "passive"))
      (node (ref "U$2") (pin "28") (pinfunction "(SCK)PB7_28") (pintype "bidirectional"))
    )
    (net (code "22") (name "ICLED_KICK") (class "Default")
      (node (ref "KICK") (pin "C") (pinfunction "C_C") (pintype "passive"))
      (node (ref "T2") (pin "3") (pinfunction "C_3") (pintype "passive"))
      (node (ref "U$2") (pin "24") (pinfunction "PB4_24") (pintype "bidirectional"))
    )
    (net (code "23") (name "ICLED_ROT") (class "Default")
      (node (ref "ROT") (pin "C") (pinfunction "C_C") (pintype "passive"))
      (node (ref "T5") (pin "3") (pinfunction "C_3") (pintype "passive"))
      (node (ref "U$2") (pin "23") (pinfunction "PB3_23") (pintype "bidirectional"))
    )
    (net (code "24") (name "KICKER") (class "Default")
      (node (ref "IC12") (pin "OUT1") (pinfunction "OUT_OUT1") (pintype "passive"))
      (node (ref "IC12") (pin "OUT2") (pinfunction "OUT_OUT2") (pintype "passive"))
      (node (ref "P6") (pin "4") (pinfunction "P_4") (pintype "passive"))
      (node (ref "R23") (pin "1") (pinfunction "1_1") (pintype "passive"))
      (node (ref "R_NULL_1") (pin "1") (pinfunction "1_1") (pintype "passive"))
    )
    (net (code "25") (name "LED_1") (class "Default")
      (node (ref "SV4") (pin "7") (pinfunction "7_7") (pintype "passive"))
    )
    (net (code "26") (name "LED_2") (class "Default")
      (node (ref "SV4") (pin "5") (pinfunction "5_5") (pintype "passive"))
    )
    (net (code "27") (name "LED_3") (class "Default")
      (node (ref "SV4") (pin "3") (pinfunction "3_3") (pintype "passive"))
    )
    (net (code "28") (name "LED_BLAU") (class "Default")
      (node (ref "SV2") (pin "9") (pinfunction "9_9") (pintype "passive"))
      (node (ref "T4") (pin "C") (pinfunction "C_C") (pintype "passive"))
    )
    (net (code "29") (name "LED_GELB") (class "Default")
      (node (ref "R_NULL_2") (pin "2") (pinfunction "2_2") (pintype "passive"))
      (node (ref "SV2") (pin "5") (pinfunction "5_5") (pintype "passive"))
    )
    (net (code "30") (name "LED_GRUEN") (class "Default")
      (node (ref "R_NULL_4") (pin "2") (pinfunction "2_2") (pintype "passive"))
      (node (ref "SV2") (pin "7") (pinfunction "7_7") (pintype "passive"))
    )
    (net (code "31") (name "LED_KICK") (class "Default")
      (node (ref "R_NULL_1") (pin "2") (pinfunction "2_2") (pintype "passive"))
      (node (ref "SV4") (pin "9") (pinfunction "9_9") (pintype "passive"))
    )
    (net (code "32") (name "LED_ROT") (class "Default")
      (node (ref "R_NULL_3") (pin "2") (pinfunction "2_2") (pintype "passive"))
      (node (ref "SV2") (pin "3") (pinfunction "3_3") (pintype "passive"))
    )
    (net (code "33") (name "MOTION") (class "Default")
      (node (ref "IC4") (pin "1") (pinfunction "OUT1_1") (pintype "passive"))
      (node (ref "IC4") (pin "5") (pinfunction "OUT2_5") (pintype "passive"))
      (node (ref "P8") (pin "3") (pinfunction "P_3") (pintype "passive"))
      (node (ref "P8") (pin "4") (pinfunction "P_4") (pintype "passive"))
      (node (ref "R15") (pin "1") (pinfunction "1_1") (pintype "passive"))
      (node (ref "R_NULL_4") (pin "1") (pinfunction "1_1") (pintype "passive"))
    )
    (net (code "34") (name "Net-(5V-PadA)") (class "Default")
      (node (ref "5V") (pin "A") (pinfunction "A_A") (pintype "passive"))
      (node (ref "R18") (pin "1") (pinfunction "1_1") (pintype "passive"))
    )
    (net (code "35") (name "Net-(12V-PadA)") (class "Default")
      (node (ref "12V") (pin "A") (pinfunction "A_A") (pintype "passive"))
      (node (ref "R28") (pin "2") (pinfunction "2_2") (pintype "passive"))
    )
    (net (code "36") (name "Net-(D1-C)") (class "Default")
      (node (ref "D1") (pin "K") (pinfunction "C_K") (pintype "passive"))
      (node (ref "D3") (pin "K") (pinfunction "C_K") (pintype "passive"))
      (node (ref "R12") (pin "1") (pinfunction "1_1") (pintype "passive"))
    )
    (net (code "37") (name "Net-(D2-C)") (class "Default")
      (node (ref "C4") (pin "2") (pinfunction "2_2") (pintype "passive"))
      (node (ref "D2") (pin "K") (pinfunction "C_K") (pintype "passive"))
      (node (ref "L2") (pin "2") (pinfunction "2_2") (pintype "passive"))
      (node (ref "U1") (pin "8") (pinfunction "VSW_8") (pintype "output"))
    )
    (net (code "38") (name "Net-(GELB-PadA)") (class "Default")
      (node (ref "GELB") (pin "A") (pinfunction "A_A") (pintype "passive"))
      (node (ref "R25") (pin "2") (pinfunction "2_2") (pintype "passive"))
    )
    (net (code "39") (name "Net-(GRÜN-PadA)") (class "Default")
      (node (ref "GRÜN") (pin "A") (pinfunction "A_A") (pintype "passive"))
      (node (ref "R27") (pin "2") (pinfunction "2_2") (pintype "passive"))
    )
    (net (code "40") (name "Net-(IC4-IN)") (class "Default")
      (node (ref "IC4") (pin "2") (pinfunction "IN_2") (pintype "input"))
      (node (ref "VR9") (pin "1") (pinfunction "C_1") (pintype "passive"))
    )
    (net (code "41") (name "Net-(KICK-PadA)") (class "Default")
      (node (ref "KICK") (pin "A") (pinfunction "A_A") (pintype "passive"))
      (node (ref "R29") (pin "2") (pinfunction "2_2") (pintype "passive"))
    )
    (net (code "42") (name "Net-(LED_BLAU-PadA)") (class "Default")
      (node (ref "LED_BLAU") (pin "A") (pinfunction "A_A") (pintype "passive"))
      (node (ref "R4") (pin "2") (pinfunction "2_2") (pintype "passive"))
    )
    (net (code "43") (name "Net-(OK1A-A)") (class "Default")
      (node (ref "OK1") (pin "1") (pinfunction "A_1") (pintype "passive"))
      (node (ref "OK1") (pin "4") (pinfunction "C_4") (pintype "passive"))
    )
    (net (code "44") (name "Net-(OK1A-C)") (class "Default")
      (node (ref "JP5") (pin "2") (pinfunction "2_2") (pintype "passive"))
      (node (ref "OK1") (pin "2") (pinfunction "C_2") (pintype "passive"))
    )
    (net (code "45") (name "Net-(OK1A-COL)") (class "Default")
      (node (ref "IC10") (pin "IN") (pinfunction "IN_IN") (pintype "input"))
      (node (ref "OK1") (pin "8") (pinfunction "COL_8") (pintype "passive"))
    )
    (net (code "46") (name "Net-(OK1A-EMIT)") (class "Default")
      (node (ref "OK1") (pin "7") (pinfunction "EMIT_7") (pintype "passive"))
      (node (ref "VR6") (pin "1") (pinfunction "C_1") (pintype "passive"))
    )
    (net (code "47") (name "Net-(OK1B-A)") (class "Default")
      (node (ref "OK1") (pin "3") (pinfunction "A_3") (pintype "passive"))
      (node (ref "R12") (pin "2") (pinfunction "2_2") (pintype "passive"))
    )
    (net (code "48") (name "Net-(OK1B-COL)") (class "Default")
      (node (ref "IC15") (pin "IN") (pinfunction "IN_IN") (pintype "input"))
      (node (ref "OK1") (pin "6") (pinfunction "COL_6") (pintype "passive"))
    )
    (net (code "49") (name "Net-(R6-Pad2)") (class "Default")
      (node (ref "R6") (pin "2") (pinfunction "2_2") (pintype "passive"))
      (node (ref "SJ1") (pin "2") (pinfunction "2_2") (pintype "passive"))
    )
    (net (code "50") (name "Net-(R7-Pad2)") (class "Default")
      (node (ref "R7") (pin "2") (pinfunction "2_2") (pintype "passive"))
      (node (ref "T4") (pin "B") (pinfunction "B_B") (pintype "passive"))
    )
    (net (code "51") (name "Net-(R26-Pad2)") (class "Default")
      (node (ref "R26") (pin "2") (pinfunction "2_2") (pintype "passive"))
      (node (ref "ROT") (pin "A") (pinfunction "A_A") (pintype "passive"))
    )
    (net (code "52") (name "Net-(RJ_1-PadP$4)") (class "Default")
      (node (ref "RJ_1") (pin "P$4") (pinfunction "P$4_P$4") (pintype "bidirectional"))
      (node (ref "RJ_2") (pin "P$4") (pinfunction "P$4_P$4") (pintype "bidirectional"))
      (node (ref "SJ2") (pin "2") (pinfunction "2_2") (pintype "passive"))
    )
    (net (code "53") (name "Net-(T1-B)") (class "Default")
      (node (ref "R5") (pin "2") (pinfunction "2_2") (pintype "passive"))
      (node (ref "T1") (pin "1") (pinfunction "B_1") (pintype "passive"))
    )
    (net (code "54") (name "Net-(T1-C)") (class "Default")
      (node (ref "T1") (pin "3") (pinfunction "C_3") (pintype "passive"))
      (node (ref "TDB-05") (pin "-") (pinfunction "2_-") (pintype "passive"))
    )
    (net (code "55") (name "Net-(T2-B)") (class "Default")
      (node (ref "R23") (pin "2") (pinfunction "2_2") (pintype "passive"))
      (node (ref "T2") (pin "1") (pinfunction "B_1") (pintype "passive"))
    )
    (net (code "56") (name "Net-(T3-B)") (class "Default")
      (node (ref "R1") (pin "2") (pinfunction "2_2") (pintype "passive"))
      (node (ref "T3") (pin "1") (pinfunction "B_1") (pintype "passive"))
    )
    (net (code "57") (name "Net-(T3-C)") (class "Default")
      (node (ref "LED_BLAU") (pin "C") (pinfunction "C_C") (pintype "passive"))
      (node (ref "R7") (pin "1") (pinfunction "1_1") (pintype "passive"))
      (node (ref "T3") (pin "3") (pinfunction "C_3") (pintype "passive"))
    )
    (net (code "58") (name "Net-(T5-B)") (class "Default")
      (node (ref "R16") (pin "2") (pinfunction "2_2") (pintype "passive"))
      (node (ref "T5") (pin "1") (pinfunction "B_1") (pintype "passive"))
    )
    (net (code "59") (name "Net-(T6-B)") (class "Default")
      (node (ref "R17") (pin "2") (pinfunction "2_2") (pintype "passive"))
      (node (ref "T6") (pin "1") (pinfunction "B_1") (pintype "passive"))
    )
    (net (code "60") (name "Net-(T7-B)") (class "Default")
      (node (ref "R15") (pin "2") (pinfunction "2_2") (pintype "passive"))
      (node (ref "T7") (pin "1") (pinfunction "B_1") (pintype "passive"))
    )
    (net (code "61") (name "Net-(U$1-RS)") (class "Default")
      (node (ref "R31") (pin "2") (pinfunction "2_2") (pintype "passive"))
      (node (ref "U$1") (pin "8") (pinfunction "RS_8") (pintype "input"))
    )
    (net (code "62") (name "Net-(U$2-AREF)") (class "Default")
      (node (ref "C14") (pin "2") (pinfunction "2_2") (pintype "passive"))
      (node (ref "U$2") (pin "21") (pinfunction "AREF_21") (pintype "bidirectional"))
    )
    (net (code "63") (name "Net-(U$2-PE1(XTAL1))") (class "Default")
      (node (ref "C11") (pin "2") (pinfunction "2_2") (pintype "passive"))
      (node (ref "Q1") (pin "1") (pinfunction "1_1") (pintype "passive"))
      (node (ref "U$2") (pin "10") (pinfunction "PE1(XTAL1)_10") (pintype "bidirectional"))
    )
    (net (code "64") (name "Net-(U$2-PE2(XTAL2))") (class "Default")
      (node (ref "C10") (pin "2") (pinfunction "2_2") (pintype "passive"))
      (node (ref "Q1") (pin "2") (pinfunction "2_2") (pintype "passive"))
      (node (ref "U$2") (pin "11") (pinfunction "PE2(XTAL2)_11") (pintype "bidirectional"))
    )
    (net (code "65") (name "Net-(U1-CB)") (class "Default")
      (node (ref "C4") (pin "1") (pinfunction "1_1") (pintype "passive"))
      (node (ref "U1") (pin "1") (pinfunction "CB_1") (pintype "input"))
    )
    (net (code "66") (name "Net-(U1-VIN)") (class "Default")
      (node (ref "C2") (pin "+") (pinfunction "+_+") (pintype "passive"))
      (node (ref "F1") (pin "2") (pinfunction "2_2") (pintype "passive"))
      (node (ref "U1") (pin "7") (pinfunction "VIN_7") (pintype "power_in"))
    )
    (net (code "67") (name "Net-(VR7-A)") (class "Default")
      (node (ref "JP2") (pin "2") (pinfunction "2_2") (pintype "passive"))
      (node (ref "VR7") (pin "3") (pinfunction "A_3") (pintype "passive"))
    )
    (net (code "68") (name "Net-(VR7-C)") (class "Default")
      (node (ref "IC11") (pin "IN") (pinfunction "IN_IN") (pintype "input"))
      (node (ref "VR7") (pin "1") (pinfunction "C_1") (pintype "passive"))
    )
    (net (code "69") (name "Net-(VR7-R)") (class "Default")
      (node (ref "R36") (pin "2") (pinfunction "2_2") (pintype "passive"))
      (node (ref "R37") (pin "1") (pinfunction "1_1") (pintype "passive"))
      (node (ref "VR7") (pin "2") (pinfunction "R_2") (pintype "passive"))
    )
    (net (code "70") (name "Net-(VR8-A)") (class "Default")
      (node (ref "JP3") (pin "2") (pinfunction "2_2") (pintype "passive"))
      (node (ref "VR8") (pin "3") (pinfunction "A_3") (pintype "passive"))
    )
    (net (code "71") (name "Net-(VR8-C)") (class "Default")
      (node (ref "IC12") (pin "IN") (pinfunction "IN_IN") (pintype "input"))
      (node (ref "VR8") (pin "1") (pinfunction "C_1") (pintype "passive"))
    )
    (net (code "72") (name "Net-(VR8-R)") (class "Default")
      (node (ref "R38") (pin "2") (pinfunction "2_2") (pintype "passive"))
      (node (ref "R39") (pin "1") (pinfunction "1_1") (pintype "passive"))
      (node (ref "VR8") (pin "2") (pinfunction "R_2") (pintype "passive"))
    )
    (net (code "73") (name "Net-(VR9-A)") (class "Default")
      (node (ref "JP4") (pin "2") (pinfunction "2_2") (pintype "passive"))
      (node (ref "VR9") (pin "3") (pinfunction "A_3") (pintype "passive"))
    )
    (net (code "74") (name "Net-(VR9-R)") (class "Default")
      (node (ref "R40") (pin "2") (pinfunction "2_2") (pintype "passive"))
      (node (ref "R41") (pin "1") (pinfunction "1_1") (pintype "passive"))
      (node (ref "VR9") (pin "2") (pinfunction "R_2") (pintype "passive"))
    )
    (net (code "75") (name "Net-(VR10-C)") (class "Default")
      (node (ref "R30") (pin "2") (pinfunction "2_2") (pintype "passive"))
      (node (ref "R35") (pin "1") (pinfunction "1_1") (pintype "passive"))
      (node (ref "VR10") (pin "1") (pinfunction "C_1") (pintype "passive"))
      (node (ref "VR6") (pin "2") (pinfunction "R_2") (pintype "passive"))
    )
    (net (code "76") (name "Net-(VR10-R)") (class "Default")
      (node (ref "R45") (pin "1") (pinfunction "1_1") (pintype "passive"))
      (node (ref "R46") (pin "2") (pinfunction "2_2") (pintype "passive"))
      (node (ref "VR10") (pin "2") (pinfunction "R_2") (pintype "passive"))
    )
    (net (code "77") (name "RST") (class "Default")
      (node (ref "ISP") (pin "5") (pinfunction "5_5") (pintype "passive"))
      (node (ref "U$2") (pin "31") (pinfunction "PE0(RESET)_31") (pintype "input"))
    )
    (net (code "78") (name "RXCAN") (class "Default")
      (node (ref "U$1") (pin "4") (pinfunction "RXD_4") (pintype "output"))
      (node (ref "U$2") (pin "7") (pinfunction "(RXCAN)PC3_7") (pintype "bidirectional"))
    )
    (net (code "79") (name "SPEAKER") (class "Default")
      (node (ref "R5") (pin "1") (pinfunction "1_1") (pintype "passive"))
      (node (ref "U$2") (pin "29") (pinfunction "PD0_29") (pintype "bidirectional"))
    )
    (net (code "80") (name "SW_1") (class "Default")
      (node (ref "SV4") (pin "8") (pinfunction "8_8") (pintype "passive"))
    )
    (net (code "81") (name "SW_1{slash}SCK_A") (class "Default")
      (node (ref "ISP") (pin "7") (pinfunction "7_7") (pintype "passive"))
      (node (ref "U$2") (pin "12") (pinfunction "(RXD)PD4_12") (pintype "bidirectional"))
    )
    (net (code "82") (name "SW_2") (class "Default")
      (node (ref "SV4") (pin "6") (pinfunction "6_6") (pintype "passive"))
    )
    (net (code "83") (name "SW_2{slash}MOSI_A") (class "Default")
      (node (ref "ISP") (pin "1") (pinfunction "1_1") (pintype "passive"))
      (node (ref "U$2") (pin "2") (pinfunction "(MOSI_A/TXD)PD3_2") (pintype "bidirectional"))
    )
    (net (code "84") (name "SW_3") (class "Default")
      (node (ref "SV4") (pin "4") (pinfunction "4_4") (pintype "passive"))
    )
    (net (code "85") (name "SW_3{slash}MISO_A") (class "Default")
      (node (ref "ISP") (pin "9") (pinfunction "9_9") (pintype "passive"))
      (node (ref "U$2") (pin "1") (pinfunction "(MISO_A)PD2_1") (pintype "bidirectional"))
    )
    (net (code "86") (name "SW_12V") (class "Default")
      (node (ref "JP5") (pin "1") (pinfunction "1_1") (pintype "passive"))
      (node (ref "SV2") (pin "4") (pinfunction "4_4") (pintype "passive"))
      (node (ref "U$2") (pin "15") (pinfunction "PD7_15") (pintype "bidirectional"))
    )
    (net (code "87") (name "SW_AKT") (class "Default")
      (node (ref "JP2") (pin "1") (pinfunction "1_1") (pintype "passive"))
      (node (ref "SJ3") (pin "1") (pinfunction "1_1") (pintype "passive"))
      (node (ref "SV2") (pin "6") (pinfunction "6_6") (pintype "passive"))
      (node (ref "U$2") (pin "8") (pinfunction "PB0_8") (pintype "bidirectional"))
    )
    (net (code "88") (name "SW_BLAU") (class "Default")
      (node (ref "SV2") (pin "10") (pinfunction "10_10") (pintype "passive"))
      (node (ref "U$2") (pin "3") (pinfunction "PC1_3") (pintype "bidirectional"))
    )
    (net (code "89") (name "SW_KICK") (class "Default")
      (node (ref "JP3") (pin "1") (pinfunction "1_1") (pintype "passive"))
      (node (ref "SJ3") (pin "2") (pinfunction "2_2") (pintype "passive"))
      (node (ref "SV4") (pin "10") (pinfunction "10_10") (pintype "passive"))
      (node (ref "U$2") (pin "25") (pinfunction "PC7_25") (pintype "bidirectional"))
    )
    (net (code "90") (name "SW_MOT") (class "Default")
      (node (ref "JP4") (pin "1") (pinfunction "1_1") (pintype "passive"))
      (node (ref "SV2") (pin "8") (pinfunction "8_8") (pintype "passive"))
      (node (ref "U$2") (pin "9") (pinfunction "PB1_9") (pintype "bidirectional"))
    )
    (net (code "91") (name "TXCAN") (class "Default")
      (node (ref "U$1") (pin "1") (pinfunction "TXD_1") (pintype "input"))
      (node (ref "U$2") (pin "6") (pinfunction "(TXCAN)PC2_6") (pintype "bidirectional"))
    )
    (net (code "92") (name "unconnected-(ISP-Pad3)") (class "Default")
      (node (ref "ISP") (pin "3") (pinfunction "3_3") (pintype "passive"))
    )
    (net (code "93") (name "unconnected-(U$1-VREF-Pad5)") (class "Default")
      (node (ref "U$1") (pin "5") (pinfunction "VREF_5") (pintype "output"))
    )
    (net (code "94") (name "unconnected-(U$2-PD1-Pad32)") (class "Default")
      (node (ref "U$2") (pin "32") (pinfunction "PD1_32") (pintype "bidirectional"))
    )
    (net (code "95") (name "unconnected-(U1-NC-Pad3)") (class "Default")
      (node (ref "U1") (pin "3") (pinfunction "NC_3") (pintype "no_connect"))
    )
    (net (code "96") (name "unconnected-(U1-NC_2-Pad2)") (class "Default")
      (node (ref "U1") (pin "2") (pinfunction "NC_2_2") (pintype "no_connect"))
    )
    (net (code "97") (name "unconnected-(U1-ON{slash}~{OFF}-Pad5)") (class "Default")
      (node (ref "U1") (pin "5") (pinfunction "ON/~{OFF}_5") (pintype "input"))
    )
  )
)
